# Main_DC-DC_Converter.net
KiCad netlist of a schematic drawn in Altium Designer
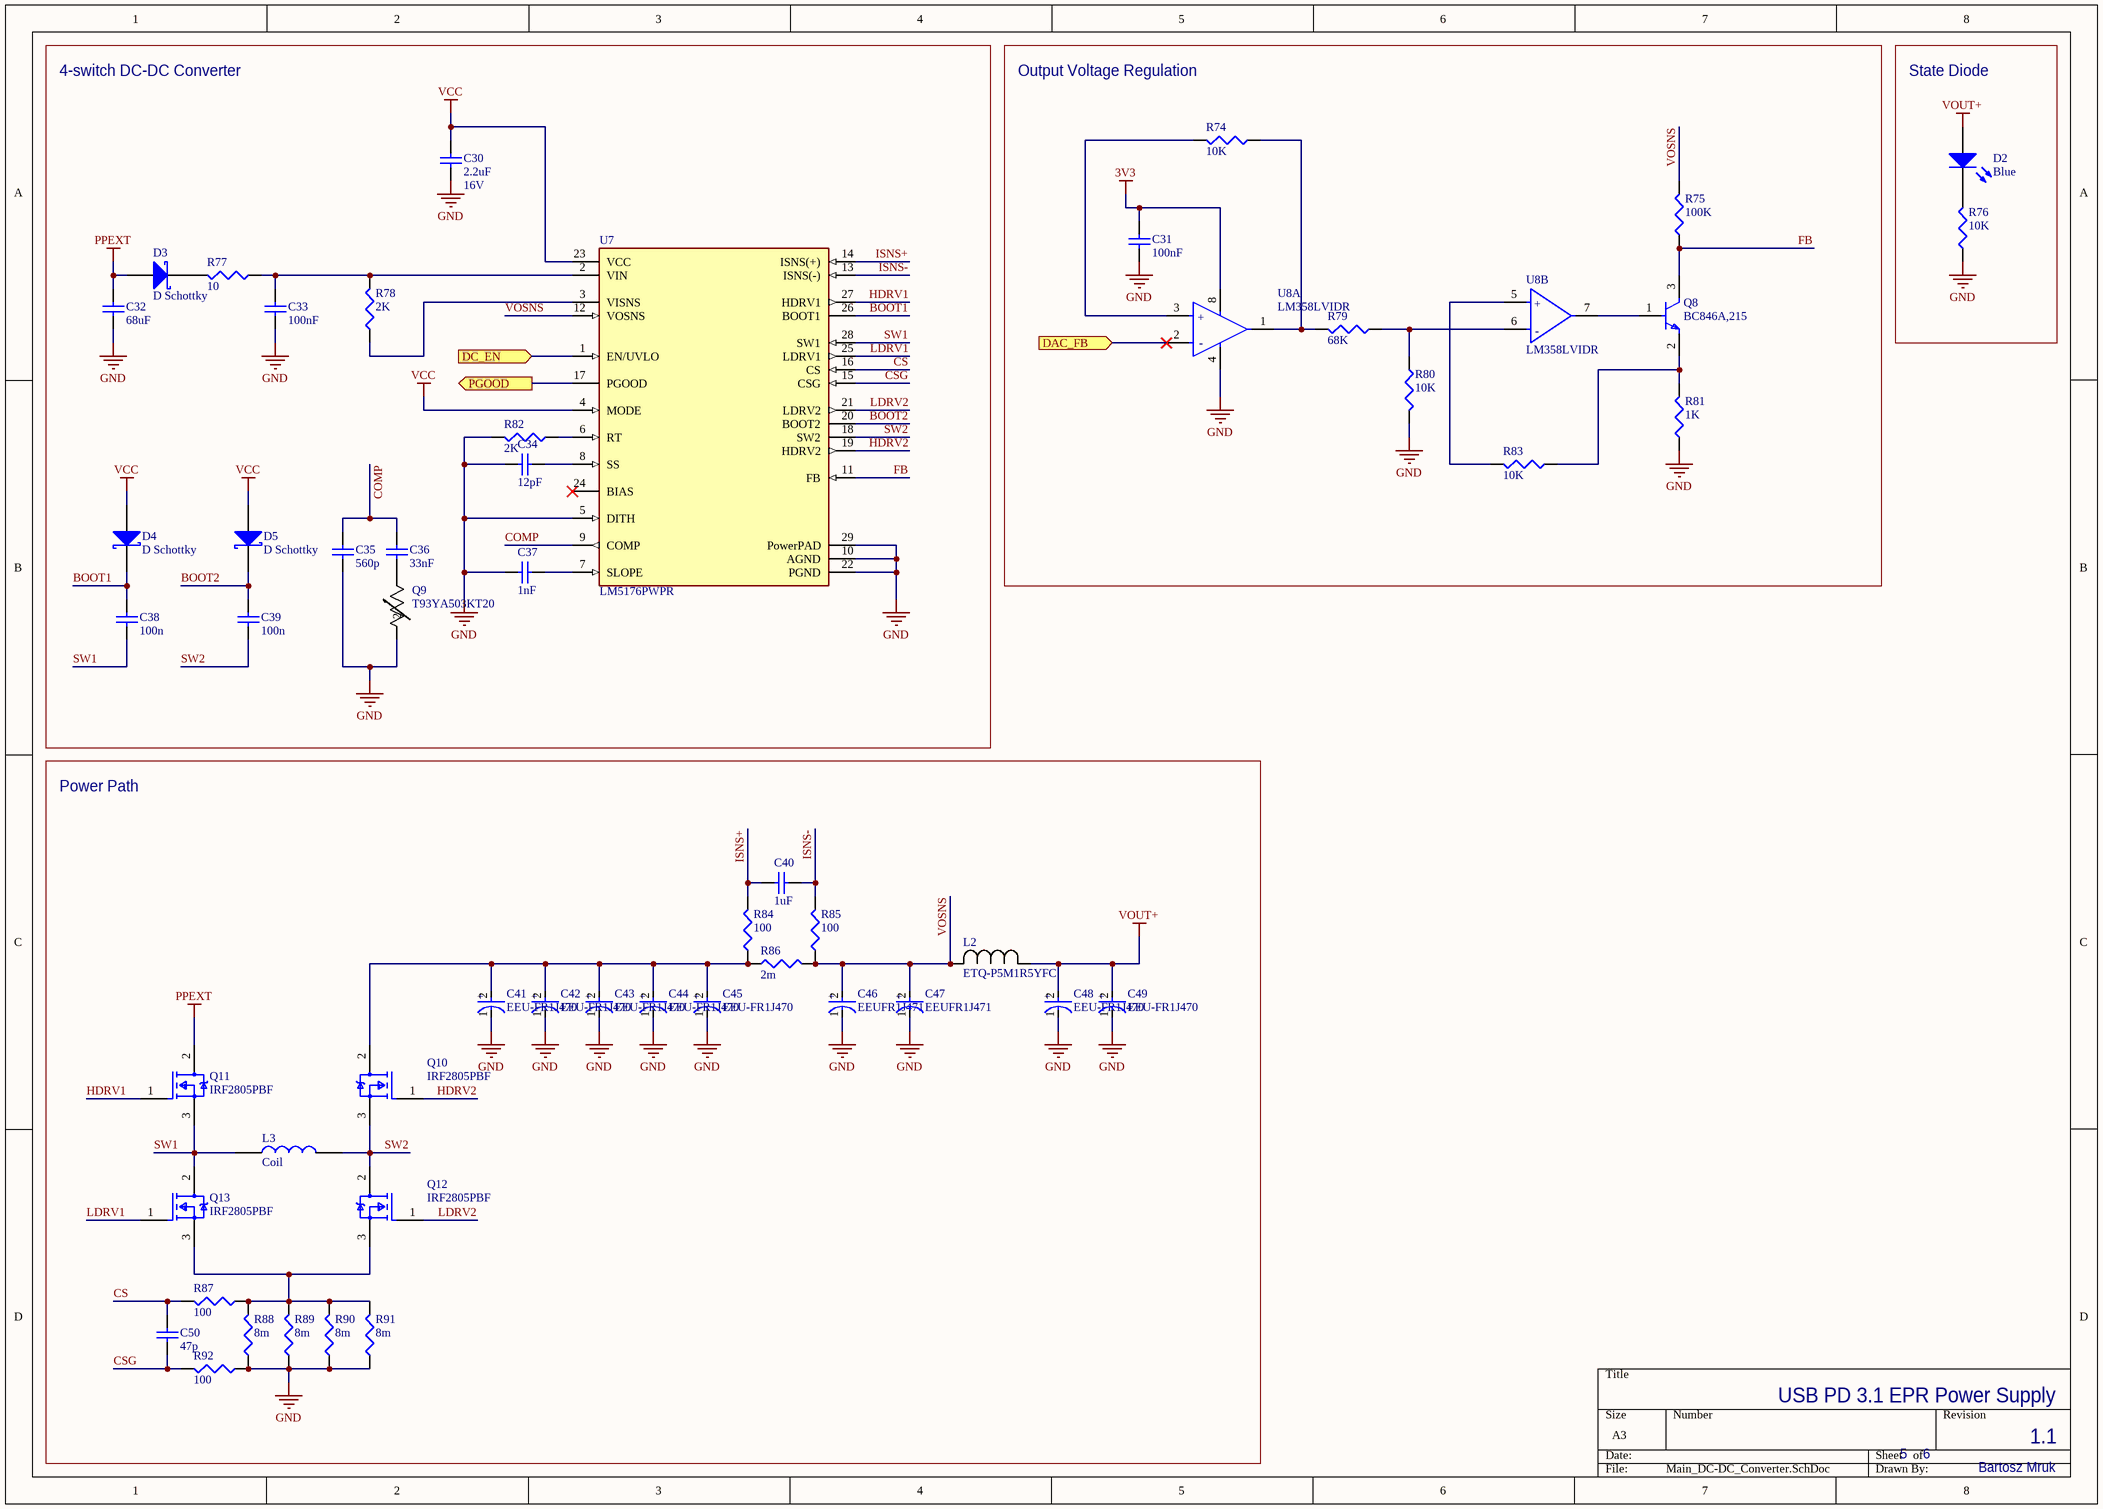
[diagram p0: Main_DC-DC_Converter.SchDoc]

(export (version "E")
  (design (tool "Eeschema 10.0.6"))
  (components
    (comp (ref "C30")
      (value "16V")
      (footprint "C1206")
      (description "Capacitor (Semiconductor SIM Model)")
      (fields (field (name "ALTIUM_VALUE") "2.2uF") (field (name "PUBLISHER") "Altium Limited"))
      (libsource (lib "Miscellaneous Devices") (part "Cap Semi"))
    )
    (comp (ref "C31")
      (value "100nF")
      (footprint "C1206")
      (description "Capacitor (Semiconductor SIM Model)")
      (fields (field (name "Comment") "Cap Semi") (field (name "PUBLISHER") "Altium Limited"))
      (libsource (lib "Miscellaneous Devices") (part "Cap Semi"))
    )
    (comp (ref "C32")
      (value "68uF")
      (footprint "C1206")
      (description "Capacitor (Semiconductor SIM Model)")
      (fields (field (name "Comment") "Cap Semi") (field (name "PUBLISHER") "Altium Limited"))
      (libsource (lib "Miscellaneous Devices") (part "Cap Semi"))
    )
    (comp (ref "C33")
      (value "100nF")
      (footprint "C1206")
      (description "Capacitor (Semiconductor SIM Model)")
      (fields (field (name "Comment") "Cap Semi") (field (name "PUBLISHER") "Altium Limited"))
      (libsource (lib "Miscellaneous Devices") (part "Cap Semi"))
    )
    (comp (ref "C34")
      (value "12pF")
      (footprint "C1206")
      (description "Capacitor (Semiconductor SIM Model)")
      (fields (field (name "Comment") "Cap Semi") (field (name "PUBLISHER") "Altium Limited"))
      (libsource (lib "Miscellaneous Devices") (part "Cap Semi"))
    )
    (comp (ref "C35")
      (value "560p")
      (footprint "C1206")
      (description "Capacitor (Semiconductor SIM Model)")
      (fields (field (name "Comment") "Cap Semi") (field (name "PUBLISHER") "Altium Limited"))
      (libsource (lib "Miscellaneous Devices") (part "Cap Semi"))
    )
    (comp (ref "C36")
      (value "33nF")
      (footprint "C1206")
      (description "Capacitor (Semiconductor SIM Model)")
      (fields (field (name "Comment") "Cap Semi") (field (name "PUBLISHER") "Altium Limited"))
      (libsource (lib "Miscellaneous Devices") (part "Cap Semi"))
    )
    (comp (ref "C37")
      (value "1nF")
      (footprint "C1206")
      (description "Capacitor (Semiconductor SIM Model)")
      (fields (field (name "Comment") "Cap Semi") (field (name "PUBLISHER") "Altium Limited"))
      (libsource (lib "Miscellaneous Devices") (part "Cap Semi"))
    )
    (comp (ref "C38")
      (value "100n")
      (footprint "C1206")
      (description "Capacitor (Semiconductor SIM Model)")
      (fields (field (name "Comment") "Cap Semi") (field (name "PUBLISHER") "Altium Limited"))
      (libsource (lib "Miscellaneous Devices") (part "Cap Semi"))
    )
    (comp (ref "C39")
      (value "100n")
      (footprint "C1206")
      (description "Capacitor (Semiconductor SIM Model)")
      (fields (field (name "Comment") "Cap Semi") (field (name "PUBLISHER") "Altium Limited"))
      (libsource (lib "Miscellaneous Devices") (part "Cap Semi"))
    )
    (comp (ref "C40")
      (value "1uF")
      (footprint "C1206")
      (description "Capacitor (Semiconductor SIM Model)")
      (fields (field (name "Comment") "Cap Semi") (field (name "PUBLISHER") "Altium Limited"))
      (libsource (lib "Miscellaneous Devices") (part "Cap Semi"))
    )
    (comp (ref "C41")
      (value "EEU-FR1J470")
      (footprint "FP-EEU-FR1J470-MFG")
      (description "CAP ALUM 47UF 20% 63V RADIAL")
      (fields (field (name "TOLERANCE") "20%") (field (name "VOLTAGE") "63V"))
      (libsource (lib "Altium Content Vault") (part "203bc49f2ac43e59fd269a8c329ed05"))
    )
    (comp (ref "C42")
      (value "EEU-FR1J470")
      (footprint "FP-EEU-FR1J470-MFG")
      (description "CAP ALUM 47UF 20% 63V RADIAL")
      (fields (field (name "TOLERANCE") "20%") (field (name "VOLTAGE") "63V"))
      (libsource (lib "Altium Content Vault") (part "203bc49f2ac43e59fd269a8c329ed05"))
    )
    (comp (ref "C43")
      (value "EEU-FR1J470")
      (footprint "FP-EEU-FR1J470-MFG")
      (description "CAP ALUM 47UF 20% 63V RADIAL")
      (fields (field (name "TOLERANCE") "20%") (field (name "VOLTAGE") "63V"))
      (libsource (lib "Altium Content Vault") (part "203bc49f2ac43e59fd269a8c329ed05"))
    )
    (comp (ref "C44")
      (value "EEU-FR1J470")
      (footprint "FP-EEU-FR1J470-MFG")
      (description "CAP ALUM 47UF 20% 63V RADIAL")
      (fields (field (name "TOLERANCE") "20%") (field (name "VOLTAGE") "63V"))
      (libsource (lib "Altium Content Vault") (part "203bc49f2ac43e59fd269a8c329ed05"))
    )
    (comp (ref "C45")
      (value "EEU-FR1J470")
      (footprint "FP-EEU-FR1J470-MFG")
      (description "CAP ALUM 47UF 20% 63V RADIAL")
      (fields (field (name "TOLERANCE") "20%") (field (name "VOLTAGE") "63V"))
      (libsource (lib "Altium Content Vault") (part "203bc49f2ac43e59fd269a8c329ed05"))
    )
    (comp (ref "C46")
      (value "EEUFR1J471")
      (footprint "FP-RAD-TH-D_12_5_0_5-L_25-MFG")
      (description "Aluminum Electrolytic Capacitors (Radial Lead Type) 470uF ±20% 63V")
      (fields (field (name "TOLERANCE") "20%") (field (name "VOLTAGE") "63V"))
      (libsource (lib "Altium Content Vault") (part "203bc49f2ac43e59fd269a8c329ed05"))
    )
    (comp (ref "C47")
      (value "EEUFR1J471")
      (footprint "FP-RAD-TH-D_12_5_0_5-L_25-MFG")
      (description "Aluminum Electrolytic Capacitors (Radial Lead Type) 470uF ±20% 63V")
      (fields (field (name "TOLERANCE") "20%") (field (name "VOLTAGE") "63V"))
      (libsource (lib "Altium Content Vault") (part "203bc49f2ac43e59fd269a8c329ed05"))
    )
    (comp (ref "C48")
      (value "EEU-FR1J470")
      (footprint "FP-EEU-FR1J470-MFG")
      (description "CAP ALUM 47UF 20% 63V RADIAL")
      (fields (field (name "TOLERANCE") "20%") (field (name "VOLTAGE") "63V"))
      (libsource (lib "Altium Content Vault") (part "203bc49f2ac43e59fd269a8c329ed05"))
    )
    (comp (ref "C49")
      (value "EEU-FR1J470")
      (footprint "FP-EEU-FR1J470-MFG")
      (description "CAP ALUM 47UF 20% 63V RADIAL")
      (fields (field (name "TOLERANCE") "20%") (field (name "VOLTAGE") "63V"))
      (libsource (lib "Altium Content Vault") (part "203bc49f2ac43e59fd269a8c329ed05"))
    )
    (comp (ref "C50")
      (value "47p")
      (footprint "C1206")
      (description "Capacitor (Semiconductor SIM Model)")
      (fields (field (name "Comment") "Cap Semi") (field (name "PUBLISHER") "Altium Limited"))
      (libsource (lib "Miscellaneous Devices") (part "Cap Semi"))
    )
    (comp (ref "D2")
      (value "Blue")
      (footprint "3.2X1.6X1.1")
      (description "Typical RED, GREEN, YELLOW, AMBER GaAs LED")
      (fields (field (name "PUBLISHER") "Altium Limited"))
      (libsource (lib "Miscellaneous Devices") (part "LED2"))
    )
    (comp (ref "D3")
      (value "D Schottky")
      (footprint "SMB")
      (description "Schottky Diode")
      (fields (field (name "PUBLISHER") "Altium Limited"))
      (libsource (lib "Miscellaneous Devices") (part "D Schottky"))
    )
    (comp (ref "D4")
      (value "D Schottky")
      (footprint "SMB")
      (description "Schottky Diode")
      (fields (field (name "PUBLISHER") "Altium Limited"))
      (libsource (lib "Miscellaneous Devices") (part "D Schottky"))
    )
    (comp (ref "D5")
      (value "D Schottky")
      (footprint "SMB")
      (description "Schottky Diode")
      (fields (field (name "PUBLISHER") "Altium Limited"))
      (libsource (lib "Miscellaneous Devices") (part "D Schottky"))
    )
    (comp (ref "L2")
      (value "ETQ-P5M1R5YFC")
      (footprint "IND_PCC-M1054M_PAN")
      (description "No Description Available")
      (fields (field (name "COPYRIGHT") "Copyright (C) 2025 Ultra Librarian. All rights reserved."))
      (libsource (lib "ETQ-P5M1R5YFC") (part "ETQ-P5M1R5YFC"))
    )
    (comp (ref "L3")
      (value "Coil")
      (footprint "744711003")
      (libsource (lib "Incductor_32-2mm") (part "Coil"))
    )
    (comp (ref "Q8")
      (value "BC846A,215")
      (footprint "FP-SOT23-IPC_A")
      (description "TRANS NPN 65V 0.1A SOT23")
      (fields
        (field (name "MANUFACTURER") "Nexperia")
        (field (name "OCTOPART") "https://octopart.com/bc846a%2C215-nexperia-78739089")
      )
      (libsource (lib "Altium Content Vault") (part "b44e953556f554d0102664c7d152cb4"))
    )
    (comp (ref "Q9")
      (value "T93YA503KT20")
      (footprint "TRIM_503KT20_VIS")
      (description "T93 YA 50K 10% TU50 e3")
      (fields (field (name "COPYRIGHT") "Copyright (C) 2025 Ultra Librarian. All rights reserved."))
      (libsource (lib "T93YA503KT20") (part "T93YA503KT20"))
    )
    (comp (ref "Q10")
      (value "IRF2805PBF")
      (footprint "FP-PG-TO220-3-MFG")
      (description "MOSFET N-CH 55V 75A TO220AB")
      (libsource (lib "Altium Content Vault") (part "535c4fe1372f32a24686ada0a8c11ba"))
    )
    (comp (ref "Q11")
      (value "IRF2805PBF")
      (footprint "FP-PG-TO220-3-MFG")
      (description "MOSFET N-CH 55V 75A TO220AB")
      (libsource (lib "Altium Content Vault") (part "535c4fe1372f32a24686ada0a8c11ba"))
    )
    (comp (ref "Q12")
      (value "IRF2805PBF")
      (footprint "FP-PG-TO220-3-MFG")
      (description "MOSFET N-CH 55V 75A TO220AB")
      (libsource (lib "Altium Content Vault") (part "535c4fe1372f32a24686ada0a8c11ba"))
    )
    (comp (ref "Q13")
      (value "IRF2805PBF")
      (footprint "FP-PG-TO220-3-MFG")
      (description "MOSFET N-CH 55V 75A TO220AB")
      (libsource (lib "Altium Content Vault") (part "535c4fe1372f32a24686ada0a8c11ba"))
    )
    (comp (ref "R74")
      (value "10K")
      (footprint "J1-0603")
      (description "Resistor")
      (fields (field (name "Comment") "Res3") (field (name "PUBLISHER") "Altium Limited"))
      (libsource (lib "Miscellaneous Devices") (part "Res3"))
    )
    (comp (ref "R75")
      (value "100K")
      (footprint "J1-0603")
      (description "Resistor")
      (fields (field (name "Comment") "Res3") (field (name "PUBLISHER") "Altium Limited"))
      (libsource (lib "Miscellaneous Devices") (part "Res3"))
    )
    (comp (ref "R76")
      (value "10K")
      (footprint "J1-0603")
      (description "Resistor")
      (fields (field (name "Comment") "Res3") (field (name "PUBLISHER") "Altium Limited"))
      (libsource (lib "Miscellaneous Devices") (part "Res3"))
    )
    (comp (ref "R77")
      (value "10")
      (footprint "J1-0603")
      (description "Resistor")
      (fields (field (name "Comment") "Res3") (field (name "PUBLISHER") "Altium Limited"))
      (libsource (lib "Miscellaneous Devices") (part "Res3"))
    )
    (comp (ref "R78")
      (value "2K")
      (footprint "J1-0603")
      (description "Resistor")
      (fields (field (name "Comment") "Res3") (field (name "PUBLISHER") "Altium Limited"))
      (libsource (lib "Miscellaneous Devices") (part "Res3"))
    )
    (comp (ref "R79")
      (value "68K")
      (footprint "J1-0603")
      (description "Resistor")
      (fields (field (name "Comment") "Res3") (field (name "PUBLISHER") "Altium Limited"))
      (libsource (lib "Miscellaneous Devices") (part "Res3"))
    )
    (comp (ref "R80")
      (value "10K")
      (footprint "J1-0603")
      (description "Resistor")
      (fields (field (name "Comment") "Res3") (field (name "PUBLISHER") "Altium Limited"))
      (libsource (lib "Miscellaneous Devices") (part "Res3"))
    )
    (comp (ref "R81")
      (value "1K")
      (footprint "J1-0603")
      (description "Resistor")
      (fields (field (name "Comment") "Res3") (field (name "PUBLISHER") "Altium Limited"))
      (libsource (lib "Miscellaneous Devices") (part "Res3"))
    )
    (comp (ref "R82")
      (value "2K")
      (footprint "J1-0603")
      (description "Resistor")
      (fields (field (name "Comment") "Res3") (field (name "PUBLISHER") "Altium Limited"))
      (libsource (lib "Miscellaneous Devices") (part "Res3"))
    )
    (comp (ref "R83")
      (value "10K")
      (footprint "J1-0603")
      (description "Resistor")
      (fields (field (name "Comment") "Res3") (field (name "PUBLISHER") "Altium Limited"))
      (libsource (lib "Miscellaneous Devices") (part "Res3"))
    )
    (comp (ref "R84")
      (value "100")
      (footprint "J1-0603")
      (description "Resistor")
      (fields (field (name "Comment") "Res3") (field (name "PUBLISHER") "Altium Limited"))
      (libsource (lib "Miscellaneous Devices") (part "Res3"))
    )
    (comp (ref "R85")
      (value "100")
      (footprint "J1-0603")
      (description "Resistor")
      (fields (field (name "Comment") "Res3") (field (name "PUBLISHER") "Altium Limited"))
      (libsource (lib "Miscellaneous Devices") (part "Res3"))
    )
    (comp (ref "R86")
      (value "2m")
      (footprint "RESC6332")
      (description "Resistor")
      (fields (field (name "Comment") "Res3") (field (name "PUBLISHER") "Altium Limited"))
      (libsource (lib "Miscellaneous Devices") (part "Res3"))
    )
    (comp (ref "R87")
      (value "100")
      (footprint "J1-0603")
      (description "Resistor")
      (fields (field (name "Comment") "Res3") (field (name "PUBLISHER") "Altium Limited"))
      (libsource (lib "Miscellaneous Devices") (part "Res3"))
    )
    (comp (ref "R88")
      (value "8m")
      (footprint "RESC6332")
      (description "Resistor")
      (fields (field (name "Comment") "Res3") (field (name "PUBLISHER") "Altium Limited"))
      (libsource (lib "Miscellaneous Devices") (part "Res3"))
    )
    (comp (ref "R89")
      (value "8m")
      (footprint "RESC6332")
      (description "Resistor")
      (fields (field (name "Comment") "Res3") (field (name "PUBLISHER") "Altium Limited"))
      (libsource (lib "Miscellaneous Devices") (part "Res3"))
    )
    (comp (ref "R90")
      (value "8m")
      (footprint "RESC6332")
      (description "Resistor")
      (fields (field (name "Comment") "Res3") (field (name "PUBLISHER") "Altium Limited"))
      (libsource (lib "Miscellaneous Devices") (part "Res3"))
    )
    (comp (ref "R91")
      (value "8m")
      (footprint "RESC6332")
      (description "Resistor")
      (fields (field (name "Comment") "Res3") (field (name "PUBLISHER") "Altium Limited"))
      (libsource (lib "Miscellaneous Devices") (part "Res3"))
    )
    (comp (ref "R92")
      (value "100")
      (footprint "J1-0603")
      (description "Resistor")
      (fields (field (name "Comment") "Res3") (field (name "PUBLISHER") "Altium Limited"))
      (libsource (lib "Miscellaneous Devices") (part "Res3"))
    )
    (comp (ref "U7")
      (value "LM5176PWPR")
      (footprint "FP-PWP0028C-IPC_C")
      (libsource (lib "Altium Content Vault") (part "76ad1e4fb8a9bbbfd4449861f717dee"))
    )
    (comp (ref "U8")
      (value "LM358LVIDR")
      (footprint "FP-D0008A-IPC_A")
      (description "IC OPAMP GP 2 CIRCUIT 8SOIC")
      (libsource (lib "Altium Content Vault") (part "d5b36c1049528187b1d2197d5d58d7e"))
    )
  )
  (nets
    (net (code "1") (name "/BOOT1") (class "Default")
      (node (ref "C38") (pin "2") (pinfunction "2_2") (pintype "passive"))
      (node (ref "D4") (pin "2") (pinfunction "K_2") (pintype "passive"))
      (node (ref "U7") (pin "26") (pinfunction "BOOT1_26") (pintype "passive"))
    )
    (net (code "2") (name "/BOOT2") (class "Default")
      (node (ref "C39") (pin "2") (pinfunction "2_2") (pintype "passive"))
      (node (ref "D5") (pin "2") (pinfunction "K_2") (pintype "passive"))
      (node (ref "U7") (pin "20") (pinfunction "BOOT2_20") (pintype "passive"))
    )
    (net (code "3") (name "/COMP") (class "Default")
      (node (ref "C35") (pin "2") (pinfunction "2_2") (pintype "passive"))
      (node (ref "C36") (pin "2") (pinfunction "2_2") (pintype "passive"))
      (node (ref "U7") (pin "9") (pinfunction "COMP_9") (pintype "output"))
    )
    (net (code "4") (name "/CS") (class "Default")
      (node (ref "C50") (pin "2") (pinfunction "2_2") (pintype "passive"))
      (node (ref "R87") (pin "2") (pinfunction "2_2") (pintype "passive"))
      (node (ref "U7") (pin "16") (pinfunction "CS_16") (pintype "input"))
    )
    (net (code "5") (name "/CSG") (class "Default")
      (node (ref "C50") (pin "1") (pinfunction "1_1") (pintype "passive"))
      (node (ref "R92") (pin "2") (pinfunction "2_2") (pintype "passive"))
      (node (ref "U7") (pin "15") (pinfunction "CSG_15") (pintype "input"))
    )
    (net (code "6") (name "/DAC_FB") (class "Default")
      (node (ref "U8") (pin "2") (pinfunction "IN1-_2") (pintype "tri_state+no_connect"))
    )
    (net (code "7") (name "/DC_EN") (class "Default")
      (node (ref "U7") (pin "1") (pinfunction "EN/UVLO_1") (pintype "input"))
    )
    (net (code "8") (name "/FB") (class "Default")
      (node (ref "Q8") (pin "3") (pinfunction "C_3") (pintype "passive"))
      (node (ref "R75") (pin "1") (pinfunction "1_1") (pintype "passive"))
      (node (ref "U7") (pin "11") (pinfunction "FB_11") (pintype "input"))
    )
    (net (code "9") (name "/HDRV1") (class "Default")
      (node (ref "Q11") (pin "1") (pinfunction "G_1") (pintype "passive"))
      (node (ref "U7") (pin "27") (pinfunction "HDRV1_27") (pintype "output"))
    )
    (net (code "10") (name "/HDRV2") (class "Default")
      (node (ref "Q10") (pin "1") (pinfunction "G_1") (pintype "passive"))
      (node (ref "U7") (pin "19") (pinfunction "HDRV2_19") (pintype "output"))
    )
    (net (code "11") (name "/ISNS+") (class "Default")
      (node (ref "C40") (pin "1") (pinfunction "1_1") (pintype "passive"))
      (node (ref "R84") (pin "2") (pinfunction "2_2") (pintype "passive"))
      (node (ref "U7") (pin "14") (pinfunction "ISNS(+)_14") (pintype "input"))
    )
    (net (code "12") (name "/ISNS-") (class "Default")
      (node (ref "C40") (pin "2") (pinfunction "2_2") (pintype "passive"))
      (node (ref "R85") (pin "2") (pinfunction "2_2") (pintype "passive"))
      (node (ref "U7") (pin "13") (pinfunction "ISNS(-)_13") (pintype "input"))
    )
    (net (code "13") (name "/LDRV1") (class "Default")
      (node (ref "Q13") (pin "1") (pinfunction "G_1") (pintype "passive"))
      (node (ref "U7") (pin "25") (pinfunction "LDRV1_25") (pintype "output"))
    )
    (net (code "14") (name "/LDRV2") (class "Default")
      (node (ref "Q12") (pin "1") (pinfunction "G_1") (pintype "passive"))
      (node (ref "U7") (pin "21") (pinfunction "LDRV2_21") (pintype "output"))
    )
    (net (code "15") (name "/PGOOD") (class "Default")
      (node (ref "U7") (pin "17") (pinfunction "PGOOD_17") (pintype "open_collector"))
    )
    (net (code "16") (name "/SW1") (class "Default")
      (node (ref "C38") (pin "1") (pinfunction "1_1") (pintype "passive"))
      (node (ref "L3") (pin "1") (pinfunction "1_1") (pintype "passive"))
      (node (ref "Q11") (pin "3") (pinfunction "S_3") (pintype "passive"))
      (node (ref "Q13") (pin "2") (pinfunction "D_2") (pintype "passive"))
      (node (ref "U7") (pin "28") (pinfunction "SW1_28") (pintype "input"))
    )
    (net (code "17") (name "/SW2") (class "Default")
      (node (ref "C39") (pin "1") (pinfunction "1_1") (pintype "passive"))
      (node (ref "L3") (pin "2") (pinfunction "2_2") (pintype "passive"))
      (node (ref "Q10") (pin "3") (pinfunction "S_3") (pintype "passive"))
      (node (ref "Q12") (pin "2") (pinfunction "D_2") (pintype "passive"))
      (node (ref "U7") (pin "18") (pinfunction "SW2_18") (pintype "passive"))
    )
    (net (code "18") (name "/VOSNS") (class "Default")
      (node (ref "C46") (pin "2") (pinfunction "A_2") (pintype "passive"))
      (node (ref "C47") (pin "2") (pinfunction "A_2") (pintype "passive"))
      (node (ref "L2") (pin "2") (pinfunction "2_2") (pintype "passive"))
      (node (ref "R75") (pin "2") (pinfunction "2_2") (pintype "passive"))
      (node (ref "R85") (pin "1") (pinfunction "1_1") (pintype "passive"))
      (node (ref "R86") (pin "2") (pinfunction "2_2") (pintype "passive"))
      (node (ref "U7") (pin "12") (pinfunction "VOSNS_12") (pintype "input"))
    )
    (net (code "19") (name "3V3") (class "Default")
      (node (ref "C31") (pin "2") (pinfunction "2_2") (pintype "passive"))
      (node (ref "U8") (pin "8") (pinfunction "V+_8") (pintype "power_in"))
    )
    (net (code "20") (name "GND") (class "Default")
      (node (ref "C30") (pin "1") (pinfunction "1_1") (pintype "passive"))
      (node (ref "C31") (pin "1") (pinfunction "1_1") (pintype "passive"))
      (node (ref "C32") (pin "1") (pinfunction "1_1") (pintype "passive"))
      (node (ref "C33") (pin "1") (pinfunction "1_1") (pintype "passive"))
      (node (ref "C34") (pin "2") (pinfunction "2_2") (pintype "passive"))
      (node (ref "C35") (pin "1") (pinfunction "1_1") (pintype "passive"))
      (node (ref "C37") (pin "2") (pinfunction "2_2") (pintype "passive"))
      (node (ref "C41") (pin "1") (pinfunction "C_1") (pintype "passive"))
      (node (ref "C42") (pin "1") (pinfunction "C_1") (pintype "passive"))
      (node (ref "C43") (pin "1") (pinfunction "C_1") (pintype "passive"))
      (node (ref "C44") (pin "1") (pinfunction "C_1") (pintype "passive"))
      (node (ref "C45") (pin "1") (pinfunction "C_1") (pintype "passive"))
      (node (ref "C46") (pin "1") (pinfunction "C_1") (pintype "passive"))
      (node (ref "C47") (pin "1") (pinfunction "C_1") (pintype "passive"))
      (node (ref "C48") (pin "1") (pinfunction "C_1") (pintype "passive"))
      (node (ref "C49") (pin "1") (pinfunction "C_1") (pintype "passive"))
      (node (ref "Q9") (pin "2") (pinfunction "2_2") (pintype "passive"))
      (node (ref "R76") (pin "1") (pinfunction "1_1") (pintype "passive"))
      (node (ref "R80") (pin "2") (pinfunction "2_2") (pintype "passive"))
      (node (ref "R81") (pin "1") (pinfunction "1_1") (pintype "passive"))
      (node (ref "R82") (pin "2") (pinfunction "2_2") (pintype "passive"))
      (node (ref "R88") (pin "1") (pinfunction "1_1") (pintype "passive"))
      (node (ref "R89") (pin "1") (pinfunction "1_1") (pintype "passive"))
      (node (ref "R90") (pin "1") (pinfunction "1_1") (pintype "passive"))
      (node (ref "R91") (pin "1") (pinfunction "1_1") (pintype "passive"))
      (node (ref "R92") (pin "1") (pinfunction "1_1") (pintype "passive"))
      (node (ref "U7") (pin "10") (pinfunction "AGND_10") (pintype "power_in"))
      (node (ref "U7") (pin "22") (pinfunction "PGND_22") (pintype "power_in"))
      (node (ref "U7") (pin "29") (pinfunction "PowerPAD_29") (pintype "passive"))
      (node (ref "U7") (pin "5") (pinfunction "DITH_5") (pintype "input"))
      (node (ref "U8") (pin "4") (pinfunction "V-_4") (pintype "power_in"))
    )
    (net (code "21") (name "Net-(C36-Pad1)") (class "Default")
      (node (ref "C36") (pin "1") (pinfunction "1_1") (pintype "passive"))
      (node (ref "Q9") (pin "1") (pinfunction "1_1") (pintype "passive"))
    )
    (net (code "22") (name "Net-(C41-A)") (class "Default")
      (node (ref "C41") (pin "2") (pinfunction "A_2") (pintype "passive"))
      (node (ref "C42") (pin "2") (pinfunction "A_2") (pintype "passive"))
      (node (ref "C43") (pin "2") (pinfunction "A_2") (pintype "passive"))
      (node (ref "C44") (pin "2") (pinfunction "A_2") (pintype "passive"))
      (node (ref "C45") (pin "2") (pinfunction "A_2") (pintype "passive"))
      (node (ref "Q10") (pin "2") (pinfunction "D_2") (pintype "passive"))
      (node (ref "R84") (pin "1") (pinfunction "1_1") (pintype "passive"))
      (node (ref "R86") (pin "1") (pinfunction "1_1") (pintype "passive"))
    )
    (net (code "23") (name "Net-(D2-K)") (class "Default")
      (node (ref "D2") (pin "2") (pinfunction "K_2") (pintype "passive"))
      (node (ref "R76") (pin "2") (pinfunction "2_2") (pintype "passive"))
    )
    (net (code "24") (name "Net-(D3-K)") (class "Default")
      (node (ref "D3") (pin "2") (pinfunction "K_2") (pintype "passive"))
      (node (ref "R77") (pin "2") (pinfunction "2_2") (pintype "passive"))
    )
    (net (code "25") (name "Net-(Q8-B)") (class "Default")
      (node (ref "Q8") (pin "1") (pinfunction "B_1") (pintype "passive"))
      (node (ref "U8") (pin "7") (pinfunction "OUT2_7") (pintype "passive"))
    )
    (net (code "26") (name "Net-(Q8-E)") (class "Default")
      (node (ref "Q8") (pin "2") (pinfunction "E_2") (pintype "passive"))
      (node (ref "R81") (pin "2") (pinfunction "2_2") (pintype "passive"))
      (node (ref "R83") (pin "1") (pinfunction "1_1") (pintype "passive"))
    )
    (net (code "27") (name "Net-(Q12-S)") (class "Default")
      (node (ref "Q12") (pin "3") (pinfunction "S_3") (pintype "passive"))
      (node (ref "Q13") (pin "3") (pinfunction "S_3") (pintype "passive"))
      (node (ref "R87") (pin "1") (pinfunction "1_1") (pintype "passive"))
      (node (ref "R88") (pin "2") (pinfunction "2_2") (pintype "passive"))
      (node (ref "R89") (pin "2") (pinfunction "2_2") (pintype "passive"))
      (node (ref "R90") (pin "2") (pinfunction "2_2") (pintype "passive"))
      (node (ref "R91") (pin "2") (pinfunction "2_2") (pintype "passive"))
    )
    (net (code "28") (name "Net-(U7-RT)") (class "Default")
      (node (ref "R82") (pin "1") (pinfunction "1_1") (pintype "passive"))
      (node (ref "U7") (pin "6") (pinfunction "RT_6") (pintype "input"))
    )
    (net (code "29") (name "Net-(U7-SLOPE)") (class "Default")
      (node (ref "C37") (pin "1") (pinfunction "1_1") (pintype "passive"))
      (node (ref "U7") (pin "7") (pinfunction "SLOPE_7") (pintype "input"))
    )
    (net (code "30") (name "Net-(U7-SS)") (class "Default")
      (node (ref "C34") (pin "1") (pinfunction "1_1") (pintype "passive"))
      (node (ref "U7") (pin "8") (pinfunction "SS_8") (pintype "input"))
    )
    (net (code "31") (name "Net-(U7-VIN)") (class "Default")
      (node (ref "C33") (pin "2") (pinfunction "2_2") (pintype "passive"))
      (node (ref "R77") (pin "1") (pinfunction "1_1") (pintype "passive"))
      (node (ref "R78") (pin "2") (pinfunction "2_2") (pintype "passive"))
      (node (ref "U7") (pin "2") (pinfunction "VIN_2") (pintype "power_in"))
    )
    (net (code "32") (name "Net-(U7-VISNS)") (class "Default")
      (node (ref "R78") (pin "1") (pinfunction "1_1") (pintype "passive"))
      (node (ref "U7") (pin "3") (pinfunction "VISNS_3") (pintype "power_in"))
    )
    (net (code "33") (name "Net-(U8A-IN1+)") (class "Default")
      (node (ref "R74") (pin "2") (pinfunction "2_2") (pintype "passive"))
      (node (ref "U8") (pin "3") (pinfunction "IN1+_3") (pintype "tri_state"))
    )
    (net (code "34") (name "Net-(U8A-OUT1)") (class "Default")
      (node (ref "R74") (pin "1") (pinfunction "1_1") (pintype "passive"))
      (node (ref "R79") (pin "2") (pinfunction "2_2") (pintype "passive"))
      (node (ref "U8") (pin "1") (pinfunction "OUT1_1") (pintype "passive"))
    )
    (net (code "35") (name "Net-(U8B-IN2+)") (class "Default")
      (node (ref "R83") (pin "2") (pinfunction "2_2") (pintype "passive"))
      (node (ref "U8") (pin "5") (pinfunction "IN2+_5") (pintype "tri_state"))
    )
    (net (code "36") (name "Net-(U8B-IN2-)") (class "Default")
      (node (ref "R79") (pin "1") (pinfunction "1_1") (pintype "passive"))
      (node (ref "R80") (pin "1") (pinfunction "1_1") (pintype "passive"))
      (node (ref "U8") (pin "6") (pinfunction "IN2-_6") (pintype "tri_state"))
    )
    (net (code "37") (name "PPEXT") (class "Default")
      (node (ref "C32") (pin "2") (pinfunction "2_2") (pintype "passive"))
      (node (ref "D3") (pin "1") (pinfunction "A_1") (pintype "passive"))
      (node (ref "Q11") (pin "2") (pinfunction "D_2") (pintype "passive"))
    )
    (net (code "38") (name "VCC") (class "Default")
      (node (ref "C30") (pin "2") (pinfunction "2_2") (pintype "passive"))
      (node (ref "D4") (pin "1") (pinfunction "A_1") (pintype "passive"))
      (node (ref "D5") (pin "1") (pinfunction "A_1") (pintype "passive"))
      (node (ref "U7") (pin "23") (pinfunction "VCC_23") (pintype "power_in"))
      (node (ref "U7") (pin "4") (pinfunction "MODE_4") (pintype "input"))
    )
    (net (code "39") (name "VOUT+") (class "Default")
      (node (ref "C48") (pin "2") (pinfunction "A_2") (pintype "passive"))
      (node (ref "C49") (pin "2") (pinfunction "A_2") (pintype "passive"))
      (node (ref "D2") (pin "1") (pinfunction "A_1") (pintype "passive"))
      (node (ref "L2") (pin "1") (pinfunction "1_1") (pintype "passive"))
    )
    (net (code "40") (name "unconnected-(U7-BIAS-Pad24)") (class "Default")
      (node (ref "U7") (pin "24") (pinfunction "BIAS_24") (pintype "passive+no_connect"))
    )
  )
)
